# polarshield_v1_4.net
KiCad netlist of a schematic drawn in EAGLE
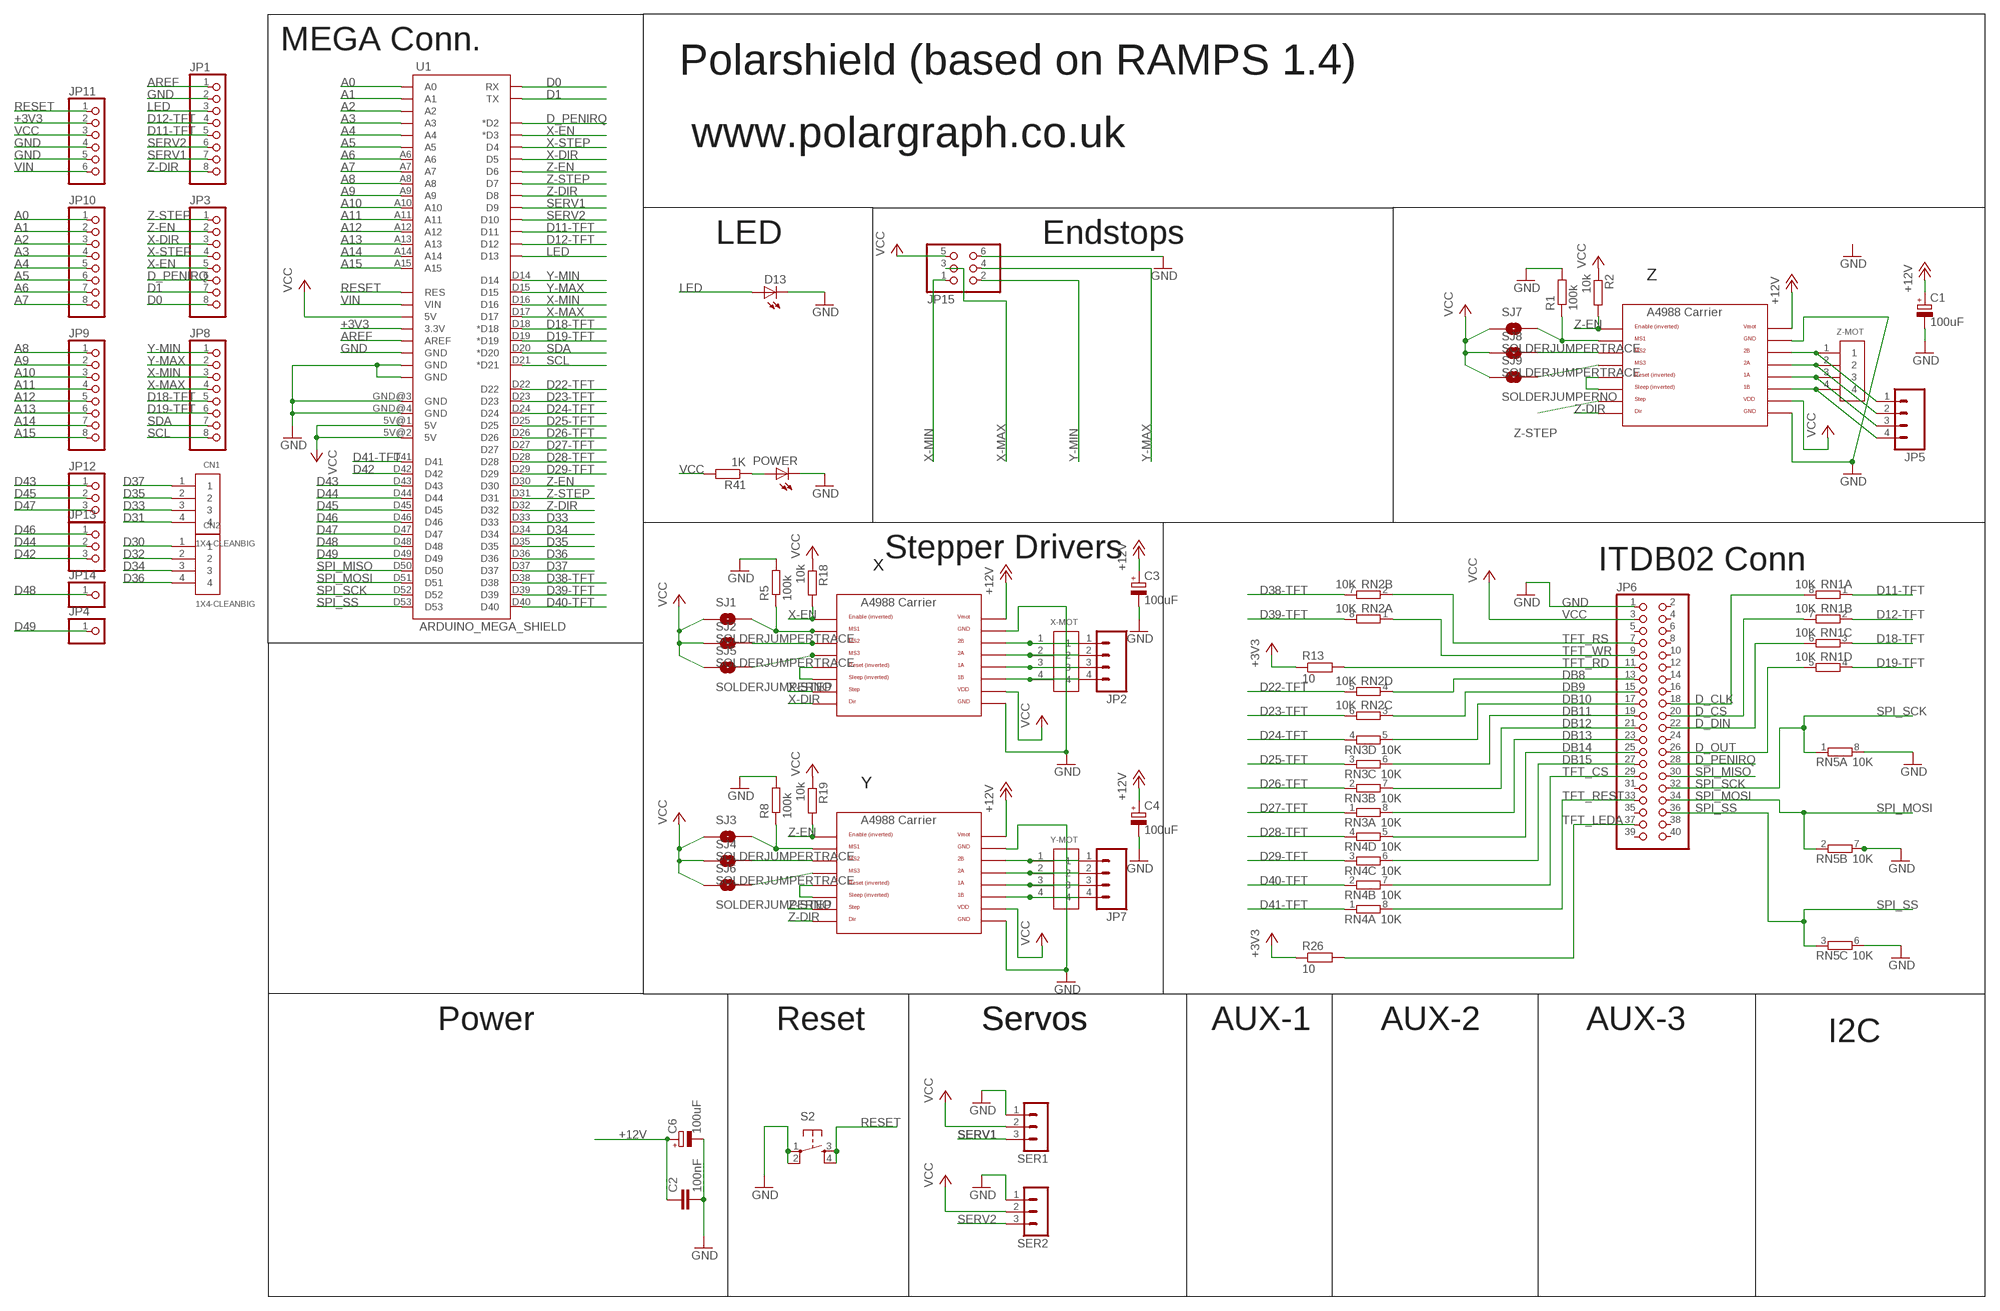
[diagram p0: schematic, sheet 1]

(export (version "E")
  (design (tool "Eeschema 10.0.6"))
  (components
    (comp (ref "C1")
      (value "100uF")
      (footprint "eagle-import:153CLV-0605")
      (libsource (lib "eagle-import") (part "CPOL-EU153CLV-0605"))
    )
    (comp (ref "C2")
      (value "100nF")
      (footprint "eagle-import:C0805")
      (libsource (lib "eagle-import") (part "C-EUC0805"))
    )
    (comp (ref "C3")
      (value "100uF")
      (footprint "eagle-import:153CLV-0605")
      (libsource (lib "eagle-import") (part "CPOL-EU153CLV-0605"))
    )
    (comp (ref "C4")
      (value "100uF")
      (footprint "eagle-import:153CLV-0605")
      (libsource (lib "eagle-import") (part "CPOL-EU153CLV-0605"))
    )
    (comp (ref "C6")
      (value "100uF")
      (footprint "eagle-import:153CLV-0605")
      (libsource (lib "eagle-import") (part "CPOL-EU153CLV-0605"))
    )
    (comp (ref "CN1")
      (value "1X4-CLEANBIG")
      (footprint "eagle-import:1X04-CLEANBIG")
      (libsource (lib "eagle-import") (part "1X4-CLEANBIG"))
    )
    (comp (ref "CN2")
      (value "1X4-CLEANBIG")
      (footprint "eagle-import:1X04-CLEANBIG")
      (libsource (lib "eagle-import") (part "1X4-CLEANBIG"))
    )
    (comp (ref "D13")
      (value "LEDCHIP-LED0805")
      (footprint "eagle-import:CHIP-LED0805")
      (libsource (lib "eagle-import") (part "LEDCHIP-LED0805"))
    )
    (comp (ref "JP1")
      (value "PINHD-1X8CLEANBIG")
      (footprint "eagle-import:1X08-CLEANBIG")
      (libsource (lib "eagle-import") (part "PINHD-1X8CLEANBIG"))
    )
    (comp (ref "JP2")
      (value "M04SCREW")
      (footprint "eagle-import:SCREWTERMINAL-3.5MM-4")
      (libsource (lib "eagle-import") (part "M04SCREW"))
    )
    (comp (ref "JP3")
      (value "PINHD-1X8CLEANBIG")
      (footprint "eagle-import:1X08-CLEANBIG")
      (libsource (lib "eagle-import") (part "PINHD-1X8CLEANBIG"))
    )
    (comp (ref "JP4")
      (value "PINHD-1X1CB")
      (footprint "eagle-import:1X01-CLEANBIG")
      (libsource (lib "eagle-import") (part "PINHD-1X1CB"))
    )
    (comp (ref "JP5")
      (value "M04SCREW")
      (footprint "eagle-import:SCREWTERMINAL-3.5MM-4")
      (libsource (lib "eagle-import") (part "M04SCREW"))
    )
    (comp (ref "JP6")
      (value "PINHD-2X20")
      (footprint "eagle-import:2X20")
      (libsource (lib "eagle-import") (part "PINHD-2X20"))
    )
    (comp (ref "JP7")
      (value "M04SCREW")
      (footprint "eagle-import:SCREWTERMINAL-3.5MM-4")
      (libsource (lib "eagle-import") (part "M04SCREW"))
    )
    (comp (ref "JP8")
      (value "PINHD-1X8CLEANBIG")
      (footprint "eagle-import:1X08-CLEANBIG")
      (libsource (lib "eagle-import") (part "PINHD-1X8CLEANBIG"))
    )
    (comp (ref "JP9")
      (value "PINHD-1X8CLEANBIG")
      (footprint "eagle-import:1X08-CLEANBIG")
      (libsource (lib "eagle-import") (part "PINHD-1X8CLEANBIG"))
    )
    (comp (ref "JP10")
      (value "PINHD-1X8CLEANBIG")
      (footprint "eagle-import:1X08-CLEANBIG")
      (libsource (lib "eagle-import") (part "PINHD-1X8CLEANBIG"))
    )
    (comp (ref "JP11")
      (value "PINHD-1X6CB")
      (footprint "eagle-import:1X06-CLEANBIG")
      (libsource (lib "eagle-import") (part "PINHD-1X6CB"))
    )
    (comp (ref "JP12")
      (value "PINHD-1X3CB")
      (footprint "eagle-import:1X03-CLEANBIG")
      (libsource (lib "eagle-import") (part "PINHD-1X3CB"))
    )
    (comp (ref "JP13")
      (value "PINHD-1X3CB")
      (footprint "eagle-import:1X03-CLEANBIG")
      (libsource (lib "eagle-import") (part "PINHD-1X3CB"))
    )
    (comp (ref "JP14")
      (value "PINHD-1X1CB")
      (footprint "eagle-import:1X01-CLEANBIG")
      (libsource (lib "eagle-import") (part "PINHD-1X1CB"))
    )
    (comp (ref "JP15")
      (value "PINHD-2X3")
      (footprint "eagle-import:2X03")
      (libsource (lib "eagle-import") (part "PINHD-2X3"))
    )
    (comp (ref "POWER")
      (value "LEDCHIP-LED0805")
      (footprint "eagle-import:CHIP-LED0805")
      (libsource (lib "eagle-import") (part "LEDCHIP-LED0805"))
    )
    (comp (ref "R1")
      (value "100k")
      (footprint "eagle-import:R0805")
      (libsource (lib "eagle-import") (part "R-EU_R0805"))
    )
    (comp (ref "R2")
      (value "10k")
      (footprint "eagle-import:R0805")
      (libsource (lib "eagle-import") (part "R-EU_R0805"))
    )
    (comp (ref "R5")
      (value "100k")
      (footprint "eagle-import:R0805")
      (libsource (lib "eagle-import") (part "R-EU_R0805"))
    )
    (comp (ref "R8")
      (value "100k")
      (footprint "eagle-import:R0805")
      (libsource (lib "eagle-import") (part "R-EU_R0805"))
    )
    (comp (ref "R13")
      (value "10")
      (footprint "eagle-import:R0805")
      (libsource (lib "eagle-import") (part "resistor_R-EU_R0805"))
    )
    (comp (ref "R18")
      (value "10k")
      (footprint "eagle-import:R0805")
      (libsource (lib "eagle-import") (part "R-EU_R0805"))
    )
    (comp (ref "R19")
      (value "10k")
      (footprint "eagle-import:R0805")
      (libsource (lib "eagle-import") (part "R-EU_R0805"))
    )
    (comp (ref "R26")
      (value "10")
      (footprint "eagle-import:R0805")
      (libsource (lib "eagle-import") (part "resistor_R-EU_R0805"))
    )
    (comp (ref "R41")
      (value "1K")
      (footprint "eagle-import:R0805")
      (libsource (lib "eagle-import") (part "R-EU_R0805"))
    )
    (comp (ref "RN1")
      (value "10K")
      (footprint "eagle-import:EXBS8V")
      (libsource (lib "eagle-import") (part "4R-NEXBS8V"))
    )
    (comp (ref "RN2")
      (value "10K")
      (footprint "eagle-import:EXBS8V")
      (libsource (lib "eagle-import") (part "4R-NEXBS8V"))
    )
    (comp (ref "RN3")
      (value "10K")
      (footprint "eagle-import:EXBS8V")
      (libsource (lib "eagle-import") (part "4R-NEXBS8V"))
    )
    (comp (ref "RN4")
      (value "10K")
      (footprint "eagle-import:EXBS8V")
      (libsource (lib "eagle-import") (part "4R-NEXBS8V"))
    )
    (comp (ref "RN5")
      (value "10K")
      (footprint "eagle-import:EXBS8V")
      (libsource (lib "eagle-import") (part "4R-NEXBS8V"))
    )
    (comp (ref "S2")
      (value "TAC_SWITCHPTH")
      (footprint "eagle-import:TACTILE-PTH")
      (libsource (lib "eagle-import") (part "TAC_SWITCHPTH"))
    )
    (comp (ref "SER1")
      (value "3PIN-HEADER")
      (footprint "eagle-import:3PIN-HEADER")
      (libsource (lib "eagle-import") (part "3PIN-HEADER"))
    )
    (comp (ref "SER2")
      (value "3PIN-HEADER")
      (footprint "eagle-import:3PIN-HEADER")
      (libsource (lib "eagle-import") (part "3PIN-HEADER"))
    )
    (comp (ref "SJ1")
      (value "SOLDERJUMPERTRACE")
      (footprint "eagle-import:SJ_2S-TRACE")
      (libsource (lib "eagle-import") (part "SOLDERJUMPERTRACE"))
    )
    (comp (ref "SJ2")
      (value "SOLDERJUMPERTRACE")
      (footprint "eagle-import:SJ_2S-TRACE")
      (libsource (lib "eagle-import") (part "SOLDERJUMPERTRACE"))
    )
    (comp (ref "SJ3")
      (value "SOLDERJUMPERTRACE")
      (footprint "eagle-import:SJ_2S-TRACE")
      (libsource (lib "eagle-import") (part "SOLDERJUMPERTRACE"))
    )
    (comp (ref "SJ4")
      (value "SOLDERJUMPERTRACE")
      (footprint "eagle-import:SJ_2S-TRACE")
      (libsource (lib "eagle-import") (part "SOLDERJUMPERTRACE"))
    )
    (comp (ref "SJ5")
      (value "SOLDERJUMPERNO")
      (footprint "eagle-import:SJ_2S-NO")
      (libsource (lib "eagle-import") (part "SOLDERJUMPERNO"))
    )
    (comp (ref "SJ6")
      (value "SOLDERJUMPERNO")
      (footprint "eagle-import:SJ_2S-NO")
      (libsource (lib "eagle-import") (part "SOLDERJUMPERNO"))
    )
    (comp (ref "SJ7")
      (value "SOLDERJUMPERTRACE")
      (footprint "eagle-import:SJ_2S-TRACE")
      (libsource (lib "eagle-import") (part "SOLDERJUMPERTRACE"))
    )
    (comp (ref "SJ8")
      (value "SOLDERJUMPERTRACE")
      (footprint "eagle-import:SJ_2S-TRACE")
      (libsource (lib "eagle-import") (part "SOLDERJUMPERTRACE"))
    )
    (comp (ref "SJ9")
      (value "SOLDERJUMPERNO")
      (footprint "eagle-import:SJ_2S-NO")
      (libsource (lib "eagle-import") (part "SOLDERJUMPERNO"))
    )
    (comp (ref "U$1")
      (value "A4988BREAKOUT")
      (footprint "eagle-import:A4988BREAKOUT")
      (libsource (lib "eagle-import") (part "A4988BREAKOUT"))
    )
    (comp (ref "U$6")
      (value "A4988BREAKOUT")
      (footprint "eagle-import:A4988BREAKOUT")
      (libsource (lib "eagle-import") (part "A4988BREAKOUT"))
    )
    (comp (ref "U$7")
      (value "A4988BREAKOUT")
      (footprint "eagle-import:A4988BREAKOUT")
      (libsource (lib "eagle-import") (part "A4988BREAKOUT"))
    )
    (comp (ref "U1")
      (value "ARDUINO_MEGA_SHIELD")
      (footprint "eagle-import:ARDUINO_MEGA_SHIELD")
      (libsource (lib "eagle-import") (part "ARDUINO_MEGA_SHIELD"))
    )
    (comp (ref "X-MOT")
      (value "1X4-BIG")
      (footprint "eagle-import:1X04-BIG")
      (libsource (lib "eagle-import") (part "1X4-BIG"))
    )
    (comp (ref "Y-MOT")
      (value "1X4-BIG")
      (footprint "eagle-import:1X04-BIG")
      (libsource (lib "eagle-import") (part "1X4-BIG"))
    )
    (comp (ref "Z-MOT")
      (value "1X4-BIG")
      (footprint "eagle-import:1X04-BIG")
      (libsource (lib "eagle-import") (part "1X4-BIG"))
    )
  )
  (nets
    (net (code "1") (name "+3V3") (class "Default")
      (node (ref "JP11") (pin "2") (pinfunction "2_2") (pintype "passive"))
      (node (ref "R13") (pin "1") (pinfunction "1_1") (pintype "passive"))
      (node (ref "R26") (pin "1") (pinfunction "1_1") (pintype "passive"))
      (node (ref "U1") (pin "3.3V") (pinfunction "3.3V_3.3V") (pintype "bidirectional"))
    )
    (net (code "2") (name "+12V") (class "Default")
      (node (ref "C1") (pin "+") (pinfunction "+_+") (pintype "passive"))
      (node (ref "C2") (pin "1") (pinfunction "1_1") (pintype "passive"))
      (node (ref "C3") (pin "+") (pinfunction "+_+") (pintype "passive"))
      (node (ref "C4") (pin "+") (pinfunction "+_+") (pintype "passive"))
      (node (ref "C6") (pin "+") (pinfunction "+_+") (pintype "passive"))
      (node (ref "U$1") (pin "VMOT") (pinfunction "VMOT_VMOT") (pintype "power_in"))
      (node (ref "U$6") (pin "VMOT") (pinfunction "VMOT_VMOT") (pintype "power_in"))
      (node (ref "U$7") (pin "VMOT") (pinfunction "VMOT_VMOT") (pintype "power_in"))
    )
    (net (code "3") (name "/A0") (class "Default")
      (node (ref "JP10") (pin "1") (pinfunction "1_1") (pintype "passive"))
      (node (ref "U1") (pin "A0") (pinfunction "A0_A0") (pintype "bidirectional"))
    )
    (net (code "4") (name "/A1") (class "Default")
      (node (ref "JP10") (pin "2") (pinfunction "2_2") (pintype "passive"))
      (node (ref "U1") (pin "A1") (pinfunction "A1_A1") (pintype "bidirectional"))
    )
    (net (code "5") (name "/A2") (class "Default")
      (node (ref "JP10") (pin "3") (pinfunction "3_3") (pintype "passive"))
      (node (ref "U1") (pin "A2") (pinfunction "A2_A2") (pintype "bidirectional"))
    )
    (net (code "6") (name "/A3") (class "Default")
      (node (ref "JP10") (pin "4") (pinfunction "4_4") (pintype "passive"))
      (node (ref "U1") (pin "A3") (pinfunction "A3_A3") (pintype "bidirectional"))
    )
    (net (code "7") (name "/A4") (class "Default")
      (node (ref "JP10") (pin "5") (pinfunction "5_5") (pintype "passive"))
      (node (ref "U1") (pin "A4") (pinfunction "A4_A4") (pintype "bidirectional"))
    )
    (net (code "8") (name "/A5") (class "Default")
      (node (ref "JP10") (pin "6") (pinfunction "6_6") (pintype "passive"))
      (node (ref "U1") (pin "A5") (pinfunction "A5_A5") (pintype "bidirectional"))
    )
    (net (code "9") (name "/A6") (class "Default")
      (node (ref "JP10") (pin "7") (pinfunction "7_7") (pintype "passive"))
      (node (ref "U1") (pin "A6") (pinfunction "A6_A6") (pintype "bidirectional"))
    )
    (net (code "10") (name "/A7") (class "Default")
      (node (ref "JP10") (pin "8") (pinfunction "8_8") (pintype "passive"))
      (node (ref "U1") (pin "A7") (pinfunction "A7_A7") (pintype "bidirectional"))
    )
    (net (code "11") (name "/A8") (class "Default")
      (node (ref "JP9") (pin "1") (pinfunction "1_1") (pintype "passive"))
      (node (ref "U1") (pin "A8") (pinfunction "A8_A8") (pintype "bidirectional"))
    )
    (net (code "12") (name "/A9") (class "Default")
      (node (ref "JP9") (pin "2") (pinfunction "2_2") (pintype "passive"))
      (node (ref "U1") (pin "A9") (pinfunction "A9_A9") (pintype "bidirectional"))
    )
    (net (code "13") (name "/A10") (class "Default")
      (node (ref "JP9") (pin "3") (pinfunction "3_3") (pintype "passive"))
      (node (ref "U1") (pin "A10") (pinfunction "A10_A10") (pintype "bidirectional"))
    )
    (net (code "14") (name "/A11") (class "Default")
      (node (ref "JP9") (pin "4") (pinfunction "4_4") (pintype "passive"))
      (node (ref "U1") (pin "A11") (pinfunction "A11_A11") (pintype "bidirectional"))
    )
    (net (code "15") (name "/A12") (class "Default")
      (node (ref "JP9") (pin "5") (pinfunction "5_5") (pintype "passive"))
      (node (ref "U1") (pin "A12") (pinfunction "A12_A12") (pintype "bidirectional"))
    )
    (net (code "16") (name "/A13") (class "Default")
      (node (ref "JP9") (pin "6") (pinfunction "6_6") (pintype "passive"))
      (node (ref "U1") (pin "A13") (pinfunction "A13_A13") (pintype "bidirectional"))
    )
    (net (code "17") (name "/A14") (class "Default")
      (node (ref "JP9") (pin "7") (pinfunction "7_7") (pintype "passive"))
      (node (ref "U1") (pin "A14") (pinfunction "A14_A14") (pintype "bidirectional"))
    )
    (net (code "18") (name "/A15") (class "Default")
      (node (ref "JP9") (pin "8") (pinfunction "8_8") (pintype "passive"))
      (node (ref "U1") (pin "A15") (pinfunction "A15_A15") (pintype "bidirectional"))
    )
    (net (code "19") (name "/AREF") (class "Default")
      (node (ref "JP1") (pin "1") (pinfunction "1_1") (pintype "passive"))
      (node (ref "U1") (pin "AREF") (pinfunction "AREF_AREF") (pintype "bidirectional"))
    )
    (net (code "20") (name "/D0") (class "Default")
      (node (ref "JP3") (pin "8") (pinfunction "8_8") (pintype "passive"))
      (node (ref "U1") (pin "RX") (pinfunction "RX_RX") (pintype "bidirectional"))
    )
    (net (code "21") (name "/D1") (class "Default")
      (node (ref "JP3") (pin "7") (pinfunction "7_7") (pintype "passive"))
      (node (ref "U1") (pin "TX") (pinfunction "TX_TX") (pintype "bidirectional"))
    )
    (net (code "22") (name "/D11-TFT") (class "Default")
      (node (ref "JP1") (pin "5") (pinfunction "5_5") (pintype "passive"))
      (node (ref "RN1") (pin "1") (pinfunction "1_1") (pintype "passive"))
      (node (ref "U1") (pin "D11") (pinfunction "D11_D11") (pintype "bidirectional"))
    )
    (net (code "23") (name "/D12-TFT") (class "Default")
      (node (ref "JP1") (pin "4") (pinfunction "4_4") (pintype "passive"))
      (node (ref "RN1") (pin "2") (pinfunction "1_2") (pintype "passive"))
      (node (ref "U1") (pin "D12") (pinfunction "D12_D12") (pintype "bidirectional"))
    )
    (net (code "24") (name "/D18-TFT") (class "Default")
      (node (ref "JP8") (pin "5") (pinfunction "5_5") (pintype "passive"))
      (node (ref "RN1") (pin "3") (pinfunction "1_3") (pintype "passive"))
      (node (ref "U1") (pin "D18") (pinfunction "*D18_D18") (pintype "bidirectional"))
    )
    (net (code "25") (name "/D19-TFT") (class "Default")
      (node (ref "JP8") (pin "6") (pinfunction "6_6") (pintype "passive"))
      (node (ref "RN1") (pin "4") (pinfunction "1_4") (pintype "passive"))
      (node (ref "U1") (pin "D19") (pinfunction "*D19_D19") (pintype "bidirectional"))
    )
    (net (code "26") (name "/D22-TFT") (class "Default")
      (node (ref "RN2") (pin "5") (pinfunction "2_5") (pintype "passive"))
      (node (ref "U1") (pin "D22") (pinfunction "D22_D22") (pintype "bidirectional"))
    )
    (net (code "27") (name "/D23-TFT") (class "Default")
      (node (ref "RN2") (pin "6") (pinfunction "2_6") (pintype "passive"))
      (node (ref "U1") (pin "D23") (pinfunction "D23_D23") (pintype "bidirectional"))
    )
    (net (code "28") (name "/D24-TFT") (class "Default")
      (node (ref "RN3") (pin "4") (pinfunction "1_4") (pintype "passive"))
      (node (ref "U1") (pin "D24") (pinfunction "D24_D24") (pintype "bidirectional"))
    )
    (net (code "29") (name "/D25-TFT") (class "Default")
      (node (ref "RN3") (pin "3") (pinfunction "1_3") (pintype "passive"))
      (node (ref "U1") (pin "D25") (pinfunction "D25_D25") (pintype "bidirectional"))
    )
    (net (code "30") (name "/D26-TFT") (class "Default")
      (node (ref "RN3") (pin "2") (pinfunction "1_2") (pintype "passive"))
      (node (ref "U1") (pin "D26") (pinfunction "D26_D26") (pintype "bidirectional"))
    )
    (net (code "31") (name "/D27-TFT") (class "Default")
      (node (ref "RN3") (pin "1") (pinfunction "1_1") (pintype "passive"))
      (node (ref "U1") (pin "D27") (pinfunction "D27_D27") (pintype "bidirectional"))
    )
    (net (code "32") (name "/D28-TFT") (class "Default")
      (node (ref "RN4") (pin "4") (pinfunction "1_4") (pintype "passive"))
      (node (ref "U1") (pin "D28") (pinfunction "D28_D28") (pintype "bidirectional"))
    )
    (net (code "33") (name "/D29-TFT") (class "Default")
      (node (ref "RN4") (pin "3") (pinfunction "1_3") (pintype "passive"))
      (node (ref "U1") (pin "D29") (pinfunction "D29_D29") (pintype "bidirectional"))
    )
    (net (code "34") (name "/D30") (class "Default")
      (node (ref "CN2") (pin "1") (pinfunction "1_1") (pintype "bidirectional"))
    )
    (net (code "35") (name "/D31") (class "Default")
      (node (ref "CN1") (pin "4") (pinfunction "4_4") (pintype "bidirectional"))
    )
    (net (code "36") (name "/D32") (class "Default")
      (node (ref "CN2") (pin "2") (pinfunction "2_2") (pintype "bidirectional"))
    )
    (net (code "37") (name "/D33") (class "Default")
      (node (ref "CN1") (pin "3") (pinfunction "3_3") (pintype "bidirectional"))
      (node (ref "U1") (pin "D33") (pinfunction "D33_D33") (pintype "bidirectional"))
    )
    (net (code "38") (name "/D34") (class "Default")
      (node (ref "CN2") (pin "3") (pinfunction "3_3") (pintype "bidirectional"))
      (node (ref "U1") (pin "D34") (pinfunction "D34_D34") (pintype "bidirectional"))
    )
    (net (code "39") (name "/D35") (class "Default")
      (node (ref "CN1") (pin "2") (pinfunction "2_2") (pintype "bidirectional"))
      (node (ref "U1") (pin "D35") (pinfunction "D35_D35") (pintype "bidirectional"))
    )
    (net (code "40") (name "/D36") (class "Default")
      (node (ref "CN2") (pin "4") (pinfunction "4_4") (pintype "bidirectional"))
      (node (ref "U1") (pin "D36") (pinfunction "D36_D36") (pintype "bidirectional"))
    )
    (net (code "41") (name "/D37") (class "Default")
      (node (ref "CN1") (pin "1") (pinfunction "1_1") (pintype "bidirectional"))
      (node (ref "U1") (pin "D37") (pinfunction "D37_D37") (pintype "bidirectional"))
    )
    (net (code "42") (name "/D38-TFT") (class "Default")
      (node (ref "RN2") (pin "7") (pinfunction "2_7") (pintype "passive"))
      (node (ref "U1") (pin "D38") (pinfunction "D38_D38") (pintype "bidirectional"))
    )
    (net (code "43") (name "/D39-TFT") (class "Default")
      (node (ref "RN2") (pin "8") (pinfunction "2_8") (pintype "passive"))
      (node (ref "U1") (pin "D39") (pinfunction "D39_D39") (pintype "bidirectional"))
    )
    (net (code "44") (name "/D40-TFT") (class "Default")
      (node (ref "RN4") (pin "2") (pinfunction "1_2") (pintype "passive"))
      (node (ref "U1") (pin "D40") (pinfunction "D40_D40") (pintype "bidirectional"))
    )
    (net (code "45") (name "/D41-TFT") (class "Default")
      (node (ref "RN4") (pin "1") (pinfunction "1_1") (pintype "passive"))
      (node (ref "U1") (pin "D41") (pinfunction "D41_D41") (pintype "bidirectional"))
    )
    (net (code "46") (name "/D42") (class "Default")
      (node (ref "JP13") (pin "3") (pinfunction "3_3") (pintype "passive"))
      (node (ref "U1") (pin "D42") (pinfunction "D42_D42") (pintype "bidirectional"))
    )
    (net (code "47") (name "/D43") (class "Default")
      (node (ref "JP12") (pin "1") (pinfunction "1_1") (pintype "passive"))
      (node (ref "U1") (pin "D43") (pinfunction "D43_D43") (pintype "bidirectional"))
    )
    (net (code "48") (name "/D44") (class "Default")
      (node (ref "JP13") (pin "2") (pinfunction "2_2") (pintype "passive"))
      (node (ref "U1") (pin "D44") (pinfunction "D44_D44") (pintype "bidirectional"))
    )
    (net (code "49") (name "/D45") (class "Default")
      (node (ref "JP12") (pin "2") (pinfunction "2_2") (pintype "passive"))
      (node (ref "U1") (pin "D45") (pinfunction "D45_D45") (pintype "bidirectional"))
    )
    (net (code "50") (name "/D46") (class "Default")
      (node (ref "JP13") (pin "1") (pinfunction "1_1") (pintype "passive"))
      (node (ref "U1") (pin "D46") (pinfunction "D46_D46") (pintype "bidirectional"))
    )
    (net (code "51") (name "/D47") (class "Default")
      (node (ref "JP12") (pin "3") (pinfunction "3_3") (pintype "passive"))
      (node (ref "U1") (pin "D47") (pinfunction "D47_D47") (pintype "bidirectional"))
    )
    (net (code "52") (name "/D48") (class "Default")
      (node (ref "JP14") (pin "1") (pinfunction "1_1") (pintype "passive"))
      (node (ref "U1") (pin "D48") (pinfunction "D48_D48") (pintype "bidirectional"))
    )
    (net (code "53") (name "/D49") (class "Default")
      (node (ref "JP4") (pin "1") (pinfunction "1_1") (pintype "passive"))
      (node (ref "U1") (pin "D49") (pinfunction "D49_D49") (pintype "bidirectional"))
    )
    (net (code "54") (name "/DB8") (class "Default")
      (node (ref "JP6") (pin "13") (pinfunction "13_13") (pintype "passive"))
      (node (ref "RN2") (pin "4") (pinfunction "1_4") (pintype "passive"))
    )
    (net (code "55") (name "/DB9") (class "Default")
      (node (ref "JP6") (pin "15") (pinfunction "15_15") (pintype "passive"))
      (node (ref "RN2") (pin "3") (pinfunction "1_3") (pintype "passive"))
    )
    (net (code "56") (name "/DB10") (class "Default")
      (node (ref "JP6") (pin "17") (pinfunction "17_17") (pintype "passive"))
      (node (ref "RN3") (pin "5") (pinfunction "2_5") (pintype "passive"))
    )
    (net (code "57") (name "/DB11") (class "Default")
      (node (ref "JP6") (pin "19") (pinfunction "19_19") (pintype "passive"))
      (node (ref "RN3") (pin "6") (pinfunction "2_6") (pintype "passive"))
    )
    (net (code "58") (name "/DB12") (class "Default")
      (node (ref "JP6") (pin "21") (pinfunction "21_21") (pintype "passive"))
      (node (ref "RN3") (pin "7") (pinfunction "2_7") (pintype "passive"))
    )
    (net (code "59") (name "/DB13") (class "Default")
      (node (ref "JP6") (pin "23") (pinfunction "23_23") (pintype "passive"))
      (node (ref "RN3") (pin "8") (pinfunction "2_8") (pintype "passive"))
    )
    (net (code "60") (name "/DB14") (class "Default")
      (node (ref "JP6") (pin "25") (pinfunction "25_25") (pintype "passive"))
      (node (ref "RN4") (pin "5") (pinfunction "2_5") (pintype "passive"))
    )
    (net (code "61") (name "/DB15") (class "Default")
      (node (ref "JP6") (pin "27") (pinfunction "27_27") (pintype "passive"))
      (node (ref "RN4") (pin "6") (pinfunction "2_6") (pintype "passive"))
    )
    (net (code "62") (name "/D_CLK") (class "Default")
      (node (ref "JP6") (pin "18") (pinfunction "18_18") (pintype "passive"))
      (node (ref "RN1") (pin "8") (pinfunction "2_8") (pintype "passive"))
    )
    (net (code "63") (name "/D_CS") (class "Default")
      (node (ref "JP6") (pin "20") (pinfunction "20_20") (pintype "passive"))
      (node (ref "RN1") (pin "7") (pinfunction "2_7") (pintype "passive"))
    )
    (net (code "64") (name "/D_DIN") (class "Default")
      (node (ref "JP6") (pin "22") (pinfunction "22_22") (pintype "passive"))
      (node (ref "RN1") (pin "6") (pinfunction "2_6") (pintype "passive"))
    )
    (net (code "65") (name "/D_OUT") (class "Default")
      (node (ref "JP6") (pin "26") (pinfunction "26_26") (pintype "passive"))
      (node (ref "RN1") (pin "5") (pinfunction "2_5") (pintype "passive"))
    )
    (net (code "66") (name "/D_PENIRQ") (class "Default")
      (node (ref "JP3") (pin "6") (pinfunction "6_6") (pintype "passive"))
      (node (ref "JP6") (pin "28") (pinfunction "28_28") (pintype "passive"))
      (node (ref "U1") (pin "D2") (pinfunction "*D2_D2") (pintype "bidirectional"))
    )
    (net (code "67") (name "/LED") (class "Default")
      (node (ref "D13") (pin "A") (pinfunction "A_A") (pintype "passive"))
      (node (ref "JP1") (pin "3") (pinfunction "3_3") (pintype "passive"))
      (node (ref "U1") (pin "D13") (pinfunction "D13_D13") (pintype "bidirectional"))
    )
    (net (code "68") (name "/RESET") (class "Default")
      (node (ref "JP11") (pin "1") (pinfunction "1_1") (pintype "passive"))
      (node (ref "S2") (pin "3") (pinfunction "3_3") (pintype "passive"))
      (node (ref "S2") (pin "4") (pinfunction "4_4") (pintype "passive"))
      (node (ref "U1") (pin "RES") (pinfunction "RES_RES") (pintype "bidirectional"))
    )
    (net (code "69") (name "/SCL") (class "Default")
      (node (ref "JP8") (pin "8") (pinfunction "8_8") (pintype "passive"))
      (node (ref "U1") (pin "D21") (pinfunction "*D21_D21") (pintype "bidirectional"))
    )
    (net (code "70") (name "/SDA") (class "Default")
      (node (ref "JP8") (pin "7") (pinfunction "7_7") (pintype "passive"))
      (node (ref "U1") (pin "D20") (pinfunction "*D20_D20") (pintype "bidirectional"))
    )
    (net (code "71") (name "/SERV1") (class "Default")
      (node (ref "JP1") (pin "7") (pinfunction "7_7") (pintype "passive"))
      (node (ref "SER1") (pin "3") (pinfunction "3_3") (pintype "passive"))
      (node (ref "U1") (pin "D9") (pinfunction "D9_D9") (pintype "bidirectional"))
    )
    (net (code "72") (name "/SERV2") (class "Default")
      (node (ref "JP1") (pin "6") (pinfunction "6_6") (pintype "passive"))
      (node (ref "SER2") (pin "3") (pinfunction "3_3") (pintype "passive"))
      (node (ref "U1") (pin "D10") (pinfunction "D10_D10") (pintype "bidirectional"))
    )
    (net (code "73") (name "/SPI_MISO") (class "Default")
      (node (ref "JP6") (pin "30") (pinfunction "30_30") (pintype "passive"))
      (node (ref "U1") (pin "D50") (pinfunction "D50_D50") (pintype "bidirectional"))
    )
    (net (code "74") (name "/SPI_MOSI") (class "Default")
      (node (ref "JP6") (pin "34") (pinfunction "34_34") (pintype "passive"))
      (node (ref "RN5") (pin "2") (pinfunction "1_2") (pintype "passive"))
      (node (ref "U1") (pin "D51") (pinfunction "D51_D51") (pintype "bidirectional"))
    )
    (net (code "75") (name "/SPI_SCK") (class "Default")
      (node (ref "JP6") (pin "32") (pinfunction "32_32") (pintype "passive"))
      (node (ref "RN5") (pin "1") (pinfunction "1_1") (pintype "passive"))
      (node (ref "U1") (pin "D52") (pinfunction "D52_D52") (pintype "bidirectional"))
    )
    (net (code "76") (name "/SPI_SS") (class "Default")
      (node (ref "JP6") (pin "36") (pinfunction "36_36") (pintype "passive"))
      (node (ref "RN5") (pin "3") (pinfunction "1_3") (pintype "passive"))
      (node (ref "U1") (pin "D53") (pinfunction "D53_D53") (pintype "bidirectional"))
    )
    (net (code "77") (name "/TFT_CS") (class "Default")
      (node (ref "JP6") (pin "29") (pinfunction "29_29") (pintype "passive"))
      (node (ref "RN4") (pin "7") (pinfunction "2_7") (pintype "passive"))
    )
    (net (code "78") (name "/TFT_LEDA") (class "Default")
      (node (ref "JP6") (pin "37") (pinfunction "37_37") (pintype "passive"))
      (node (ref "R26") (pin "2") (pinfunction "2_2") (pintype "passive"))
    )
    (net (code "79") (name "/TFT_RD") (class "Default")
      (node (ref "JP6") (pin "11") (pinfunction "11_11") (pintype "passive"))
      (node (ref "R13") (pin "2") (pinfunction "2_2") (pintype "passive"))
    )
    (net (code "80") (name "/TFT_REST") (class "Default")
      (node (ref "JP6") (pin "33") (pinfunction "33_33") (pintype "passive"))
      (node (ref "RN4") (pin "8") (pinfunction "2_8") (pintype "passive"))
    )
    (net (code "81") (name "/TFT_RS") (class "Default")
      (node (ref "JP6") (pin "7") (pinfunction "7_7") (pintype "passive"))
      (node (ref "RN2") (pin "2") (pinfunction "1_2") (pintype "passive"))
    )
    (net (code "82") (name "/TFT_WR") (class "Default")
      (node (ref "JP6") (pin "9") (pinfunction "9_9") (pintype "passive"))
      (node (ref "RN2") (pin "1") (pinfunction "1_1") (pintype "passive"))
    )
    (net (code "83") (name "/VIN") (class "Default")
      (node (ref "JP11") (pin "6") (pinfunction "6_6") (pintype "passive"))
      (node (ref "U1") (pin "VIN") (pinfunction "VIN_VIN") (pintype "bidirectional"))
    )
    (net (code "84") (name "/X-DIR") (class "Default")
      (node (ref "JP3") (pin "3") (pinfunction "3_3") (pintype "passive"))
      (node (ref "U$6") (pin "DIR") (pinfunction "DIR_DIR") (pintype "input"))
      (node (ref "U1") (pin "D5") (pinfunction "D5_D5") (pintype "bidirectional"))
    )
    (net (code "85") (name "/X-EN") (class "Default")
      (node (ref "JP3") (pin "5") (pinfunction "5_5") (pintype "passive"))
      (node (ref "R18") (pin "2") (pinfunction "2_2") (pintype "passive"))
      (node (ref "U$6") (pin "EN") (pinfunction "EN_EN") (pintype "input"))
      (node (ref "U1") (pin "D3") (pinfunction "*D3_D3") (pintype "bidirectional"))
    )
    (net (code "86") (name "/X-MAX") (class "Default")
      (node (ref "JP15") (pin "3") (pinfunction "3_3") (pintype "passive"))
      (node (ref "JP8") (pin "4") (pinfunction "4_4") (pintype "passive"))
      (node (ref "U1") (pin "D17") (pinfunction "D17_D17") (pintype "bidirectional"))
    )
    (net (code "87") (name "/X-MIN") (class "Default")
      (node (ref "JP15") (pin "1") (pinfunction "1_1") (pintype "passive"))
      (node (ref "JP8") (pin "3") (pinfunction "3_3") (pintype "passive"))
      (node (ref "U1") (pin "D16") (pinfunction "D16_D16") (pintype "bidirectional"))
    )
    (net (code "88") (name "/X-STEP") (class "Default")
      (node (ref "JP3") (pin "4") (pinfunction "4_4") (pintype "passive"))
      (node (ref "U$6") (pin "STEP") (pinfunction "STEP_STEP") (pintype "input"))
      (node (ref "U1") (pin "D4") (pinfunction "D4_D4") (pintype "bidirectional"))
    )
    (net (code "89") (name "/Y-MAX") (class "Default")
      (node (ref "JP15") (pin "4") (pinfunction "4_4") (pintype "passive"))
      (node (ref "JP8") (pin "2") (pinfunction "2_2") (pintype "passive"))
      (node (ref "U1") (pin "D15") (pinfunction "D15_D15") (pintype "bidirectional"))
    )
    (net (code "90") (name "/Y-MIN") (class "Default")
      (node (ref "JP15") (pin "2") (pinfunction "2_2") (pintype "passive"))
      (node (ref "JP8") (pin "1") (pinfunction "1_1") (pintype "passive"))
      (node (ref "U1") (pin "D14") (pinfunction "D14_D14") (pintype "bidirectional"))
    )
    (net (code "91") (name "/Z-DIR") (class "Default")
      (node (ref "JP1") (pin "8") (pinfunction "8_8") (pintype "passive"))
      (node (ref "U$1") (pin "DIR") (pinfunction "DIR_DIR") (pintype "input"))
      (node (ref "U$7") (pin "DIR") (pinfunction "DIR_DIR") (pintype "input"))
      (node (ref "U1") (pin "D32") (pinfunction "D32_D32") (pintype "bidirectional"))
      (node (ref "U1") (pin "D8") (pinfunction "D8_D8") (pintype "bidirectional"))
    )
    (net (code "92") (name "/Z-EN") (class "Default")
      (node (ref "JP3") (pin "2") (pinfunction "2_2") (pintype "passive"))
      (node (ref "R19") (pin "2") (pinfunction "2_2") (pintype "passive"))
      (node (ref "R2") (pin "2") (pinfunction "2_2") (pintype "passive"))
      (node (ref "U$1") (pin "EN") (pinfunction "EN_EN") (pintype "input"))
      (node (ref "U$7") (pin "EN") (pinfunction "EN_EN") (pintype "input"))
      (node (ref "U1") (pin "D30") (pinfunction "D30_D30") (pintype "bidirectional"))
      (node (ref "U1") (pin "D6") (pinfunction "D6_D6") (pintype "bidirectional"))
    )
    (net (code "93") (name "/Z-STEP") (class "Default")
      (node (ref "JP3") (pin "1") (pinfunction "1_1") (pintype "passive"))
      (node (ref "U$1") (pin "STEP") (pinfunction "STEP_STEP") (pintype "input"))
      (node (ref "U$7") (pin "STEP") (pinfunction "STEP_STEP") (pintype "input"))
      (node (ref "U1") (pin "D31") (pinfunction "D31_D31") (pintype "bidirectional"))
      (node (ref "U1") (pin "D7") (pinfunction "D7_D7") (pintype "bidirectional"))
    )
    (net (code "94") (name "GND") (class "Default")
      (node (ref "C1") (pin "-") (pinfunction "-_-") (pintype "passive"))
      (node (ref "C2") (pin "2") (pinfunction "2_2") (pintype "passive"))
      (node (ref "C3") (pin "-") (pinfunction "-_-") (pintype "passive"))
      (node (ref "C4") (pin "-") (pinfunction "-_-") (pintype "passive"))
      (node (ref "C6") (pin "-") (pinfunction "-_-") (pintype "passive"))
      (node (ref "D13") (pin "C") (pinfunction "C_C") (pintype "passive"))
      (node (ref "JP1") (pin "2") (pinfunction "2_2") (pintype "passive"))
      (node (ref "JP11") (pin "4") (pinfunction "4_4") (pintype "passive"))
      (node (ref "JP11") (pin "5") (pinfunction "5_5") (pintype "passive"))
      (node (ref "JP15") (pin "6") (pinfunction "6_6") (pintype "passive"))
      (node (ref "JP6") (pin "1") (pinfunction "1_1") (pintype "passive"))
      (node (ref "POWER") (pin "C") (pinfunction "C_C") (pintype "passive"))
      (node (ref "R1") (pin "2") (pinfunction "2_2") (pintype "passive"))
      (node (ref "R5") (pin "2") (pinfunction "2_2") (pintype "passive"))
      (node (ref "R8") (pin "2") (pinfunction "2_2") (pintype "passive"))
      (node (ref "RN5") (pin "6") (pinfunction "2_6") (pintype "passive"))
      (node (ref "RN5") (pin "7") (pinfunction "2_7") (pintype "passive"))
      (node (ref "RN5") (pin "8") (pinfunction "2_8") (pintype "passive"))
      (node (ref "S2") (pin "1") (pinfunction "1_1") (pintype "passive"))
      (node (ref "S2") (pin "2") (pinfunction "2_2") (pintype "passive"))
      (node (ref "SER1") (pin "1") (pinfunction "1_1") (pintype "passive"))
      (node (ref "SER2") (pin "1") (pinfunction "1_1") (pintype "passive"))
      (node (ref "U$1") (pin "GND") (pinfunction "GND_GND") (pintype "power_in"))
      (node (ref "U$1") (pin "GND@0") (pinfunction "GND_GND@0") (pintype "power_in"))
      (node (ref "U$6") (pin "GND") (pinfunction "GND_GND") (pintype "power_in"))
      (node (ref "U$6") (pin "GND@0") (pinfunction "GND_GND@0") (pintype "power_in"))
      (node (ref "U$7") (pin "GND") (pinfunction "GND_GND") (pintype "power_in"))
      (node (ref "U$7") (pin "GND@0") (pinfunction "GND_GND@0") (pintype "power_in"))
      (node (ref "U1") (pin "GND@0") (pinfunction "GND_GND@0") (pintype "power_in"))
      (node (ref "U1") (pin "GND@1") (pinfunction "GND_GND@1") (pintype "power_in"))
      (node (ref "U1") (pin "GND@2") (pinfunction "GND_GND@2") (pintype "power_in"))
      (node (ref "U1") (pin "GND@3") (pinfunction "GND_GND@3") (pintype "power_in"))
      (node (ref "U1") (pin "GND@4") (pinfunction "GND_GND@4") (pintype "power_in"))
    )
    (net (code "95") (name "Net-(JP2-Pad1)") (class "Default")
      (node (ref "JP2") (pin "1") (pinfunction "1_1") (pintype "passive"))
      (node (ref "U$6") (pin "2B") (pinfunction "2B_2B") (pintype "output"))
      (node (ref "X-MOT") (pin "1") (pinfunction "1_1") (pintype "bidirectional"))
    )
    (net (code "96") (name "Net-(JP2-Pad2)") (class "Default")
      (node (ref "JP2") (pin "2") (pinfunction "2_2") (pintype "passive"))
      (node (ref "U$6") (pin "2A") (pinfunction "2A_2A") (pintype "output"))
      (node (ref "X-MOT") (pin "2") (pinfunction "2_2") (pintype "bidirectional"))
    )
    (net (code "97") (name "Net-(JP2-Pad3)") (class "Default")
      (node (ref "JP2") (pin "3") (pinfunction "3_3") (pintype "passive"))
      (node (ref "U$6") (pin "1A") (pinfunction "1A_1A") (pintype "output"))
      (node (ref "X-MOT") (pin "3") (pinfunction "3_3") (pintype "bidirectional"))
    )
    (net (code "98") (name "Net-(JP2-Pad4)") (class "Default")
      (node (ref "JP2") (pin "4") (pinfunction "4_4") (pintype "passive"))
      (node (ref "U$6") (pin "1B") (pinfunction "1B_1B") (pintype "output"))
      (node (ref "X-MOT") (pin "4") (pinfunction "4_4") (pintype "bidirectional"))
    )
    (net (code "99") (name "Net-(JP5-Pad1)") (class "Default")
      (node (ref "JP5") (pin "1") (pinfunction "1_1") (pintype "passive"))
      (node (ref "U$1") (pin "2B") (pinfunction "2B_2B") (pintype "output"))
      (node (ref "Z-MOT") (pin "1") (pinfunction "1_1") (pintype "bidirectional"))
    )
    (net (code "100") (name "Net-(JP5-Pad2)") (class "Default")
      (node (ref "JP5") (pin "2") (pinfunction "2_2") (pintype "passive"))
      (node (ref "U$1") (pin "2A") (pinfunction "2A_2A") (pintype "output"))
      (node (ref "Z-MOT") (pin "2") (pinfunction "2_2") (pintype "bidirectional"))
    )
    (net (code "101") (name "Net-(JP5-Pad3)") (class "Default")
      (node (ref "JP5") (pin "3") (pinfunction "3_3") (pintype "passive"))
      (node (ref "U$1") (pin "1A") (pinfunction "1A_1A") (pintype "output"))
      (node (ref "Z-MOT") (pin "3") (pinfunction "3_3") (pintype "bidirectional"))
    )
    (net (code "102") (name "Net-(JP5-Pad4)") (class "Default")
      (node (ref "JP5") (pin "4") (pinfunction "4_4") (pintype "passive"))
      (node (ref "U$1") (pin "1B") (pinfunction "1B_1B") (pintype "output"))
      (node (ref "Z-MOT") (pin "4") (pinfunction "4_4") (pintype "bidirectional"))
    )
    (net (code "103") (name "Net-(JP7-Pad1)") (class "Default")
      (node (ref "JP7") (pin "1") (pinfunction "1_1") (pintype "passive"))
      (node (ref "U$7") (pin "2B") (pinfunction "2B_2B") (pintype "output"))
      (node (ref "Y-MOT") (pin "1") (pinfunction "1_1") (pintype "bidirectional"))
    )
    (net (code "104") (name "Net-(JP7-Pad2)") (class "Default")
      (node (ref "JP7") (pin "2") (pinfunction "2_2") (pintype "passive"))
      (node (ref "U$7") (pin "2A") (pinfunction "2A_2A") (pintype "output"))
      (node (ref "Y-MOT") (pin "2") (pinfunction "2_2") (pintype "bidirectional"))
    )
    (net (code "105") (name "Net-(JP7-Pad3)") (class "Default")
      (node (ref "JP7") (pin "3") (pinfunction "3_3") (pintype "passive"))
      (node (ref "U$7") (pin "1A") (pinfunction "1A_1A") (pintype "output"))
      (node (ref "Y-MOT") (pin "3") (pinfunction "3_3") (pintype "bidirectional"))
    )
    (net (code "106") (name "Net-(JP7-Pad4)") (class "Default")
      (node (ref "JP7") (pin "4") (pinfunction "4_4") (pintype "passive"))
      (node (ref "U$7") (pin "1B") (pinfunction "1B_1B") (pintype "output"))
      (node (ref "Y-MOT") (pin "4") (pinfunction "4_4") (pintype "bidirectional"))
    )
    (net (code "107") (name "Net-(POWER-PadA)") (class "Default")
      (node (ref "POWER") (pin "A") (pinfunction "A_A") (pintype "passive"))
      (node (ref "R41") (pin "1") (pinfunction "1_1") (pintype "passive"))
    )
    (net (code "108") (name "Net-(R1-Pad1)") (class "Default")
      (node (ref "R1") (pin "1") (pinfunction "1_1") (pintype "passive"))
      (node (ref "SJ7") (pin "2") (pinfunction "2_2") (pintype "passive"))
      (node (ref "U$1") (pin "MS1") (pinfunction "MS1_MS1") (pintype "input"))
    )
    (net (code "109") (name "Net-(R5-Pad1)") (class "Default")
      (node (ref "R5") (pin "1") (pinfunction "1_1") (pintype "passive"))
      (node (ref "SJ1") (pin "2") (pinfunction "2_2") (pintype "passive"))
      (node (ref "U$6") (pin "MS1") (pinfunction "MS1_MS1") (pintype "input"))
    )
    (net (code "110") (name "Net-(R8-Pad1)") (class "Default")
      (node (ref "R8") (pin "1") (pinfunction "1_1") (pintype "passive"))
      (node (ref "SJ3") (pin "2") (pinfunction "2_2") (pintype "passive"))
      (node (ref "U$7") (pin "MS1") (pinfunction "MS1_MS1") (pintype "input"))
    )
    (net (code "111") (name "Net-(SJ2-Pad2)") (class "Default")
      (node (ref "SJ2") (pin "2") (pinfunction "2_2") (pintype "passive"))
      (node (ref "U$6") (pin "MS2") (pinfunction "MS2_MS2") (pintype "input"))
    )
    (net (code "112") (name "Net-(SJ4-Pad2)") (class "Default")
      (node (ref "SJ4") (pin "2") (pinfunction "2_2") (pintype "passive"))
      (node (ref "U$7") (pin "MS2") (pinfunction "MS2_MS2") (pintype "input"))
    )
    (net (code "113") (name "Net-(SJ5-Pad2)") (class "Default")
      (node (ref "SJ5") (pin "2") (pinfunction "2_2") (pintype "passive"))
      (node (ref "U$6") (pin "MS3") (pinfunction "MS3_MS3") (pintype "input"))
    )
    (net (code "114") (name "Net-(SJ6-Pad2)") (class "Default")
      (node (ref "SJ6") (pin "2") (pinfunction "2_2") (pintype "passive"))
      (node (ref "U$7") (pin "MS3") (pinfunction "MS3_MS3") (pintype "input"))
    )
    (net (code "115") (name "Net-(SJ8-Pad2)") (class "Default")
      (node (ref "SJ8") (pin "2") (pinfunction "2_2") (pintype "passive"))
      (node (ref "U$1") (pin "MS2") (pinfunction "MS2_MS2") (pintype "input"))
    )
    (net (code "116") (name "Net-(SJ9-Pad2)") (class "Default")
      (node (ref "SJ9") (pin "2") (pinfunction "2_2") (pintype "passive"))
      (node (ref "U$1") (pin "MS3") (pinfunction "MS3_MS3") (pintype "input"))
    )
    (net (code "117") (name "Net-(U$1-SLEEP)") (class "Default")
      (node (ref "U$1") (pin "RST") (pinfunction "RST_RST") (pintype "input"))
      (node (ref "U$1") (pin "SLP") (pinfunction "SLEEP_SLP") (pintype "input"))
    )
    (net (code "118") (name "Net-(U$6-SLEEP)") (class "Default")
      (node (ref "U$6") (pin "RST") (pinfunction "RST_RST") (pintype "input"))
      (node (ref "U$6") (pin "SLP") (pinfunction "SLEEP_SLP") (pintype "input"))
    )
    (net (code "119") (name "Net-(U$7-SLEEP)") (class "Default")
      (node (ref "U$7") (pin "RST") (pinfunction "RST_RST") (pintype "input"))
      (node (ref "U$7") (pin "SLP") (pinfunction "SLEEP_SLP") (pintype "input"))
    )
    (net (code "120") (name "VCC") (class "Default")
      (node (ref "JP11") (pin "3") (pinfunction "3_3") (pintype "passive"))
      (node (ref "JP15") (pin "5") (pinfunction "5_5") (pintype "passive"))
      (node (ref "JP6") (pin "3") (pinfunction "3_3") (pintype "passive"))
      (node (ref "R18") (pin "1") (pinfunction "1_1") (pintype "passive"))
      (node (ref "R19") (pin "1") (pinfunction "1_1") (pintype "passive"))
      (node (ref "R2") (pin "1") (pinfunction "1_1") (pintype "passive"))
      (node (ref "R41") (pin "2") (pinfunction "2_2") (pintype "passive"))
      (node (ref "SER1") (pin "2") (pinfunction "2_2") (pintype "passive"))
      (node (ref "SER2") (pin "2") (pinfunction "2_2") (pintype "passive"))
      (node (ref "SJ1") (pin "1") (pinfunction "1_1") (pintype "passive"))
      (node (ref "SJ2") (pin "1") (pinfunction "1_1") (pintype "passive"))
      (node (ref "SJ3") (pin "1") (pinfunction "1_1") (pintype "passive"))
      (node (ref "SJ4") (pin "1") (pinfunction "1_1") (pintype "passive"))
      (node (ref "SJ5") (pin "1") (pinfunction "1_1") (pintype "passive"))
      (node (ref "SJ6") (pin "1") (pinfunction "1_1") (pintype "passive"))
      (node (ref "SJ7") (pin "1") (pinfunction "1_1") (pintype "passive"))
      (node (ref "SJ8") (pin "1") (pinfunction "1_1") (pintype "passive"))
      (node (ref "SJ9") (pin "1") (pinfunction "1_1") (pintype "passive"))
      (node (ref "U$1") (pin "VDD") (pinfunction "VDD_VDD") (pintype "power_in"))
      (node (ref "U$6") (pin "VDD") (pinfunction "VDD_VDD") (pintype "power_in"))
      (node (ref "U$7") (pin "VDD") (pinfunction "VDD_VDD") (pintype "power_in"))
      (node (ref "U1") (pin "5V@0") (pinfunction "5V_5V@0") (pintype "power_in"))
      (node (ref "U1") (pin "5V@1") (pinfunction "5V_5V@1") (pintype "power_in"))
      (node (ref "U1") (pin "5V@2") (pinfunction "5V_5V@2") (pintype "power_in"))
    )
    (net (code "121") (name "unconnected-(JP6-Pad2)") (class "Default")
      (node (ref "JP6") (pin "2") (pinfunction "2_2") (pintype "passive"))
    )
    (net (code "122") (name "unconnected-(JP6-Pad4)") (class "Default")
      (node (ref "JP6") (pin "4") (pinfunction "4_4") (pintype "passive"))
    )
    (net (code "123") (name "unconnected-(JP6-Pad5)") (class "Default")
      (node (ref "JP6") (pin "5") (pinfunction "5_5") (pintype "passive"))
    )
    (net (code "124") (name "unconnected-(JP6-Pad6)") (class "Default")
      (node (ref "JP6") (pin "6") (pinfunction "6_6") (pintype "passive"))
    )
    (net (code "125") (name "unconnected-(JP6-Pad8)") (class "Default")
      (node (ref "JP6") (pin "8") (pinfunction "8_8") (pintype "passive"))
    )
    (net (code "126") (name "unconnected-(JP6-Pad10)") (class "Default")
      (node (ref "JP6") (pin "10") (pinfunction "10_10") (pintype "passive"))
    )
    (net (code "127") (name "unconnected-(JP6-Pad12)") (class "Default")
      (node (ref "JP6") (pin "12") (pinfunction "12_12") (pintype "passive"))
    )
    (net (code "128") (name "unconnected-(JP6-Pad14)") (class "Default")
      (node (ref "JP6") (pin "14") (pinfunction "14_14") (pintype "passive"))
    )
    (net (code "129") (name "unconnected-(JP6-Pad16)") (class "Default")
      (node (ref "JP6") (pin "16") (pinfunction "16_16") (pintype "passive"))
    )
    (net (code "130") (name "unconnected-(JP6-Pad24)") (class "Default")
      (node (ref "JP6") (pin "24") (pinfunction "24_24") (pintype "passive"))
    )
    (net (code "131") (name "unconnected-(JP6-Pad31)") (class "Default")
      (node (ref "JP6") (pin "31") (pinfunction "31_31") (pintype "passive"))
    )
    (net (code "132") (name "unconnected-(JP6-Pad35)") (class "Default")
      (node (ref "JP6") (pin "35") (pinfunction "35_35") (pintype "passive"))
    )
    (net (code "133") (name "unconnected-(JP6-Pad38)") (class "Default")
      (node (ref "JP6") (pin "38") (pinfunction "38_38") (pintype "passive"))
    )
    (net (code "134") (name "unconnected-(JP6-Pad39)") (class "Default")
      (node (ref "JP6") (pin "39") (pinfunction "39_39") (pintype "passive"))
    )
    (net (code "135") (name "unconnected-(JP6-Pad40)") (class "Default")
      (node (ref "JP6") (pin "40") (pinfunction "40_40") (pintype "passive"))
    )
  )
)
